# Main.net
KiCad netlist of a schematic drawn in Altium Designer
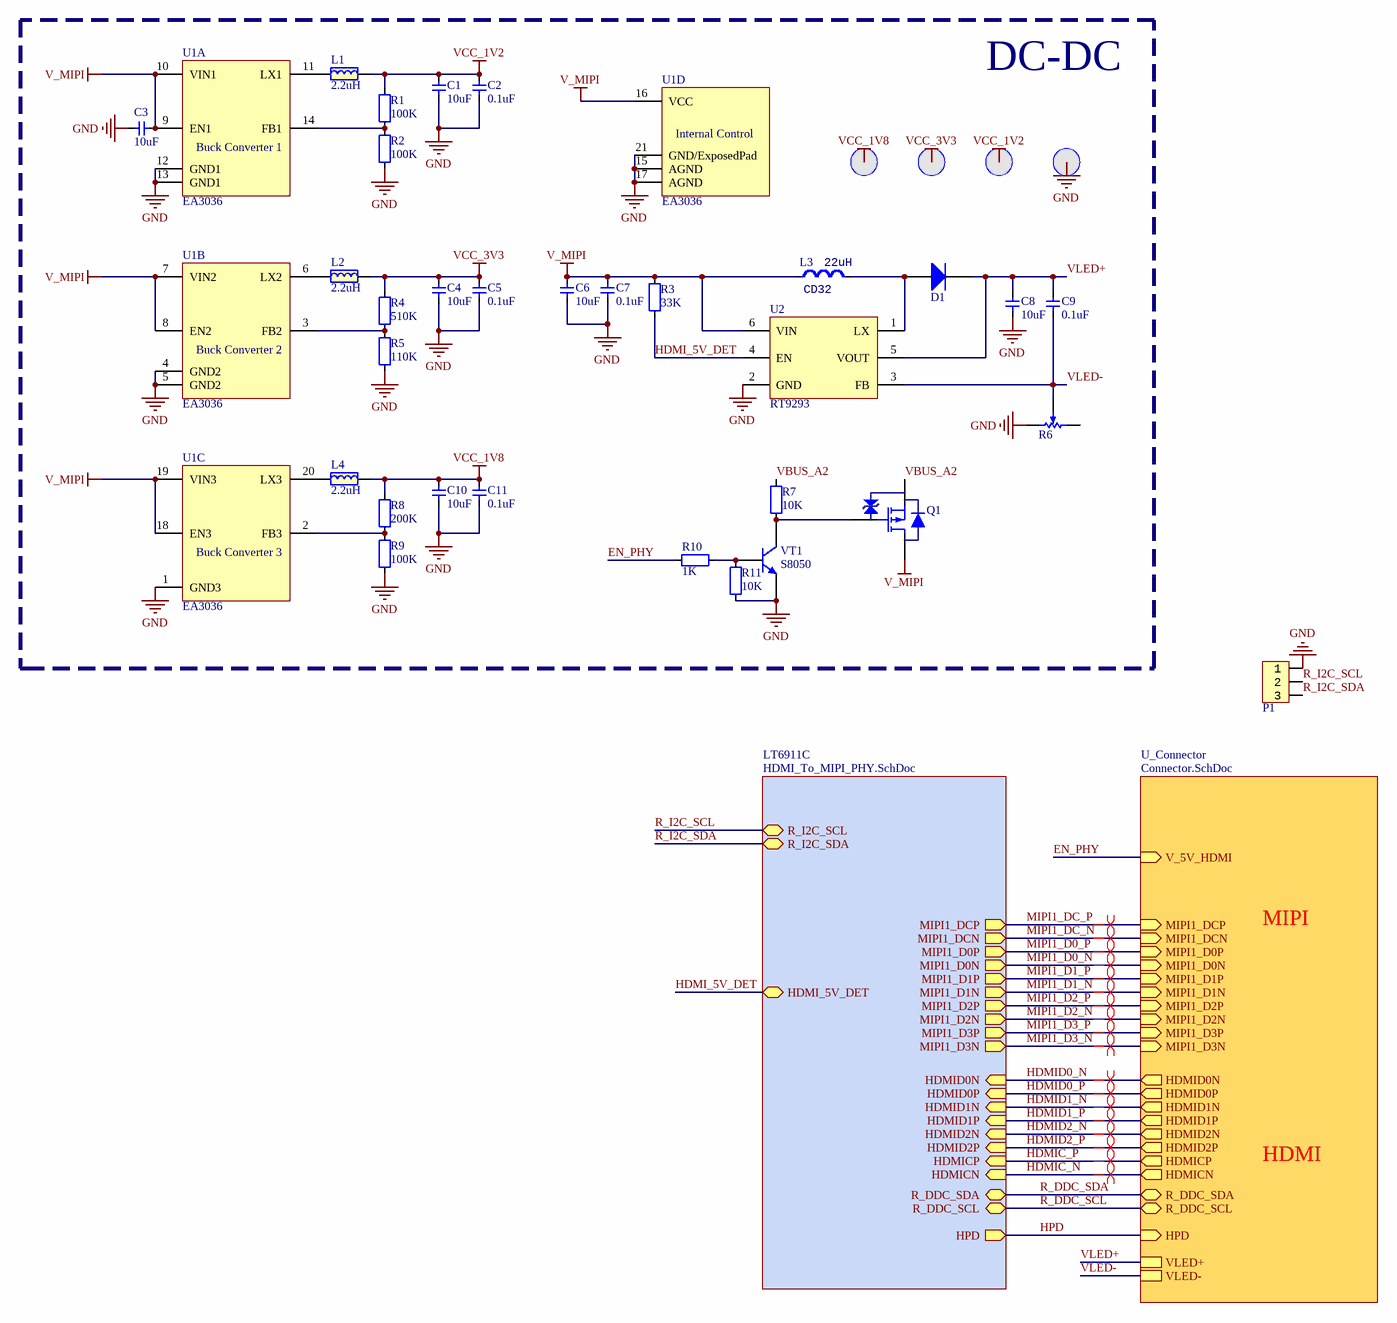
[diagram p0: Main.SchDoc]

(export (version "E")
  (design (tool "Eeschema 10.0.6"))
  (components
    (comp (ref "C1")
      (value "10uF")
      (footprint "CAP_0402")
      (description "Capacitor")
      (libsource (lib "MyPcbLib") (part "电容-0402"))
    )
    (comp (ref "C2")
      (value "0.1uF")
      (footprint "CAP_0402")
      (description "Capacitor")
      (libsource (lib "MyPcbLib") (part "电容-0402"))
    )
    (comp (ref "C3")
      (value "10uF")
      (footprint "CAP_0402")
      (description "Capacitor")
      (libsource (lib "MyPcbLib") (part "电容-0402"))
    )
    (comp (ref "C4")
      (value "10uF")
      (footprint "CAP_0402")
      (description "Capacitor")
      (libsource (lib "MyPcbLib") (part "电容-0402"))
    )
    (comp (ref "C5")
      (value "0.1uF")
      (footprint "CAP_0402")
      (description "Capacitor")
      (libsource (lib "MyPcbLib") (part "电容-0402"))
    )
    (comp (ref "C6")
      (value "10uF")
      (footprint "CAP_0402")
      (description "Capacitor")
      (libsource (lib "MyPcbLib") (part "电容-0402"))
    )
    (comp (ref "C7")
      (value "0.1uF")
      (footprint "CAP_0402")
      (description "Capacitor")
      (libsource (lib "MyPcbLib") (part "电容-0402"))
    )
    (comp (ref "C8")
      (value "10uF")
      (footprint "CAP_0402")
      (description "Capacitor")
      (libsource (lib "MyPcbLib") (part "电容-0402"))
    )
    (comp (ref "C9")
      (value "0.1uF")
      (footprint "CAP_0402")
      (description "Capacitor")
      (libsource (lib "MyPcbLib") (part "电容-0402"))
    )
    (comp (ref "C10")
      (value "10uF")
      (footprint "CAP_0402")
      (description "Capacitor")
      (libsource (lib "MyPcbLib") (part "电容-0402"))
    )
    (comp (ref "C11")
      (value "0.1uF")
      (footprint "CAP_0402")
      (description "Capacitor")
      (libsource (lib "MyPcbLib") (part "电容-0402"))
    )
    (comp (ref "D1")
      (value "二极管-5B5817WS")
      (footprint "SOD-323")
      (description "40V")
      (libsource (lib "MyPcbLib") (part "二极管-5B5817WS"))
    )
    (comp (ref "L1")
      (value "2.2uH")
      (footprint "2520-L")
      (description "磁珠")
      (libsource (lib "MyPcbLib") (part "电感-2520"))
    )
    (comp (ref "L2")
      (value "2.2uH")
      (footprint "2520-L")
      (description "磁珠")
      (libsource (lib "MyPcbLib") (part "电感-2520"))
    )
    (comp (ref "L3")
      (value "22uH")
      (footprint "IND_CD32")
      (description "Inductor")
      (fields (field (name "TYPE") "CD32") (field (name "Comment") "CD32"))
      (libsource (lib "KitSprout") (part "Ind_CD32"))
    )
    (comp (ref "L4")
      (value "2.2uH")
      (footprint "2520-L")
      (description "磁珠")
      (libsource (lib "MyPcbLib") (part "电感-2520"))
    )
    (comp (ref "P1")
      (value "HDR1x3_2.54")
      (footprint "HDR1X3_2.54_90")
      (description "Header")
      (libsource (lib "KitSprout") (part "HDR1x3_2.54T"))
    )
    (comp (ref "Q1")
      (value "AO3415A")
      (footprint "SOT23-3")
      (description "MOSFET")
      (fields (field (name "PUBLISHER") "Altium Limited"))
      (libsource (lib "MyPcbLib") (part "AO3415A"))
    )
    (comp (ref "R1")
      (value "100K")
      (footprint "RES_0402")
      (description "Resistor")
      (libsource (lib "") (part "电阻-0402_1"))
    )
    (comp (ref "R2")
      (value "100K")
      (footprint "RES_0402")
      (description "Resistor")
      (libsource (lib "") (part "电阻-0402_1"))
    )
    (comp (ref "R3")
      (value "33K")
      (footprint "RES_0402")
      (description "Resistor")
      (libsource (lib "") (part "电阻-0402_1"))
    )
    (comp (ref "R4")
      (value "510K")
      (footprint "RES_0402")
      (description "Resistor")
      (libsource (lib "") (part "电阻-0402_1"))
    )
    (comp (ref "R5")
      (value "110K")
      (footprint "RES_0402")
      (description "Resistor")
      (libsource (lib "") (part "电阻-0402_1"))
    )
    (comp (ref "R6")
      (value "电位器-贴片")
      (footprint "贴片电位器 3*3")
      (fields (field (name "PUBLISHER") "Altium Limited"))
      (libsource (lib "MyPcbLib") (part "电位器-贴片"))
    )
    (comp (ref "R7")
      (value "10K")
      (footprint "RES_0402")
      (description "Resistor")
      (libsource (lib "") (part "电阻-0402_1"))
    )
    (comp (ref "R8")
      (value "200K")
      (footprint "RES_0402")
      (description "Resistor")
      (libsource (lib "") (part "电阻-0402_1"))
    )
    (comp (ref "R9")
      (value "100K")
      (footprint "RES_0402")
      (description "Resistor")
      (libsource (lib "") (part "电阻-0402_1"))
    )
    (comp (ref "R10")
      (value "1K")
      (footprint "RES_0402")
      (description "Resistor")
      (libsource (lib "") (part "电阻-0402_2"))
    )
    (comp (ref "R11")
      (value "10K")
      (footprint "RES_0402")
      (description "Resistor")
      (libsource (lib "MyPcbLib") (part "电阻-0402"))
    )
    (comp (ref "T1") (value "测试点") (footprint "TEST_PT") (libsource (lib "MyPcbLib") (part "测试点")))
    (comp (ref "T2") (value "测试点") (footprint "TEST_PT") (libsource (lib "MyPcbLib") (part "测试点")))
    (comp (ref "T3") (value "测试点") (footprint "TEST_PT") (libsource (lib "MyPcbLib") (part "测试点")))
    (comp (ref "T4") (value "测试点") (footprint "TEST_PT") (libsource (lib "MyPcbLib") (part "测试点")))
    (comp (ref "U1") (value "EA3036") (footprint "QFN-20") (libsource (lib "MyPcbLib") (part "EA3036")))
    (comp (ref "U2")
      (value "RT9293")
      (footprint "SOT23-6")
      (description "LCD-LED Driver")
      (libsource (lib "mLib") (part "RT9293"))
    )
    (comp (ref "VT1")
      (value "S8050")
      (footprint "SMT_TRIODE_NPN")
      (description "Surface mount NPN transistor, package SOT-23")
      (libsource (lib "MyPcbLib") (part "SMT_TRIODE_NPN"))
    )
  )
  (nets
    (net (code "1") (name "/EN_PHY") (class "Default")
      (node (ref "R10") (pin "2") (pinfunction "2_2") (pintype "passive"))
    )
    (net (code "10") (name "/HDMI_5V_DET") (class "Default")
      (node (ref "R3") (pin "1") (pinfunction "1_1") (pintype "passive"))
      (node (ref "U2") (pin "4") (pinfunction "EN_4") (pintype "passive"))
    )
    (net (code "24") (name "/R_I2C_SCL") (class "Default")
      (node (ref "P1") (pin "2") (pinfunction "2_2") (pintype "passive"))
    )
    (net (code "25") (name "/R_I2C_SDA") (class "Default")
      (node (ref "P1") (pin "3") (pinfunction "3_3") (pintype "passive"))
    )
    (net (code "26") (name "/VBUS_A2") (class "Default")
      (node (ref "Q1") (pin "2") (pinfunction "S_2") (pintype "passive"))
      (node (ref "R7") (pin "2") (pinfunction "2_2") (pintype "passive"))
    )
    (net (code "27") (name "/VLED+") (class "Default")
      (node (ref "C8") (pin "2") (pinfunction "2_2") (pintype "passive"))
      (node (ref "C9") (pin "2") (pinfunction "2_2") (pintype "passive"))
      (node (ref "D1") (pin "2") (pinfunction "K_2") (pintype "passive"))
      (node (ref "U2") (pin "5") (pinfunction "VOUT_5") (pintype "passive"))
    )
    (net (code "28") (name "/VLED-") (class "Default")
      (node (ref "C9") (pin "1") (pinfunction "1_1") (pintype "passive"))
      (node (ref "R6") (pin "3") (pinfunction "W_3") (pintype "passive"))
      (node (ref "U2") (pin "3") (pinfunction "FB_3") (pintype "passive"))
    )
    (net (code "29") (name "GND") (class "Default")
      (node (ref "C1") (pin "2") (pinfunction "2_2") (pintype "passive"))
      (node (ref "C10") (pin "2") (pinfunction "2_2") (pintype "passive"))
      (node (ref "C11") (pin "2") (pinfunction "2_2") (pintype "passive"))
      (node (ref "C2") (pin "2") (pinfunction "2_2") (pintype "passive"))
      (node (ref "C3") (pin "1") (pinfunction "1_1") (pintype "passive"))
      (node (ref "C4") (pin "2") (pinfunction "2_2") (pintype "passive"))
      (node (ref "C5") (pin "2") (pinfunction "2_2") (pintype "passive"))
      (node (ref "C6") (pin "1") (pinfunction "1_1") (pintype "passive"))
      (node (ref "C7") (pin "1") (pinfunction "1_1") (pintype "passive"))
      (node (ref "C8") (pin "1") (pinfunction "1_1") (pintype "passive"))
      (node (ref "P1") (pin "1") (pinfunction "1_1") (pintype "passive"))
      (node (ref "R11") (pin "2") (pinfunction "2_2") (pintype "passive"))
      (node (ref "R2") (pin "1") (pinfunction "1_1") (pintype "passive"))
      (node (ref "R5") (pin "1") (pinfunction "1_1") (pintype "passive"))
      (node (ref "R6") (pin "1") (pinfunction "+_1") (pintype "passive"))
      (node (ref "R9") (pin "1") (pinfunction "1_1") (pintype "passive"))
      (node (ref "T4") (pin "0") (pinfunction "0_0") (pintype "passive"))
      (node (ref "U1") (pin "1") (pinfunction "GND3_1") (pintype "power_in"))
      (node (ref "U1") (pin "12") (pinfunction "GND1_12") (pintype "power_in"))
      (node (ref "U1") (pin "13") (pinfunction "GND1_13") (pintype "power_in"))
      (node (ref "U1") (pin "15") (pinfunction "AGND_15") (pintype "power_in"))
      (node (ref "U1") (pin "17") (pinfunction "AGND_17") (pintype "power_in"))
      (node (ref "U1") (pin "21") (pinfunction "GND/ExposedPad_21") (pintype "power_in"))
      (node (ref "U1") (pin "4") (pinfunction "GND2_4") (pintype "power_in"))
      (node (ref "U1") (pin "5") (pinfunction "GND2_5") (pintype "power_in"))
      (node (ref "U2") (pin "2") (pinfunction "GND_2") (pintype "passive"))
      (node (ref "VT1") (pin "2") (pinfunction "E_2") (pintype "passive"))
    )
    (net (code "30") (name "Net-(D1-A)") (class "Default")
      (node (ref "D1") (pin "1") (pinfunction "A_1") (pintype "passive"))
      (node (ref "L3") (pin "2") (pinfunction "2_2") (pintype "passive"))
      (node (ref "U2") (pin "1") (pinfunction "LX_1") (pintype "passive"))
    )
    (net (code "31") (name "Net-(Q1-G)") (class "Default")
      (node (ref "Q1") (pin "1") (pinfunction "G_1") (pintype "passive"))
      (node (ref "R7") (pin "1") (pinfunction "1_1") (pintype "passive"))
      (node (ref "VT1") (pin "3") (pinfunction "C_3") (pintype "passive"))
    )
    (net (code "32") (name "Net-(U1A-FB1)") (class "Default")
      (node (ref "R1") (pin "1") (pinfunction "1_1") (pintype "passive"))
      (node (ref "R2") (pin "2") (pinfunction "2_2") (pintype "passive"))
      (node (ref "U1") (pin "14") (pinfunction "FB1_14") (pintype "passive"))
    )
    (net (code "33") (name "Net-(U1A-LX1)") (class "Default")
      (node (ref "L1") (pin "1") (pintype "passive"))
      (node (ref "U1") (pin "11") (pinfunction "LX1_11") (pintype "passive"))
    )
    (net (code "34") (name "Net-(U1B-FB2)") (class "Default")
      (node (ref "R4") (pin "1") (pinfunction "1_1") (pintype "passive"))
      (node (ref "R5") (pin "2") (pinfunction "2_2") (pintype "passive"))
      (node (ref "U1") (pin "3") (pinfunction "FB2_3") (pintype "passive"))
    )
    (net (code "35") (name "Net-(U1B-LX2)") (class "Default")
      (node (ref "L2") (pin "1") (pintype "passive"))
      (node (ref "U1") (pin "6") (pinfunction "LX2_6") (pintype "passive"))
    )
    (net (code "36") (name "Net-(U1C-FB3)") (class "Default")
      (node (ref "R8") (pin "1") (pinfunction "1_1") (pintype "passive"))
      (node (ref "R9") (pin "2") (pinfunction "2_2") (pintype "passive"))
      (node (ref "U1") (pin "2") (pinfunction "FB3_2") (pintype "passive"))
    )
    (net (code "37") (name "Net-(U1C-LX3)") (class "Default")
      (node (ref "L4") (pin "1") (pintype "passive"))
      (node (ref "U1") (pin "20") (pinfunction "LX3_20") (pintype "passive"))
    )
    (net (code "38") (name "Net-(VT1-B)") (class "Default")
      (node (ref "R10") (pin "1") (pinfunction "1_1") (pintype "passive"))
      (node (ref "R11") (pin "1") (pinfunction "1_1") (pintype "passive"))
      (node (ref "VT1") (pin "1") (pinfunction "B_1") (pintype "passive"))
    )
    (net (code "39") (name "VCC_1V2") (class "Default")
      (node (ref "C1") (pin "1") (pinfunction "1_1") (pintype "passive"))
      (node (ref "C2") (pin "1") (pinfunction "1_1") (pintype "passive"))
      (node (ref "L1") (pin "2") (pinfunction "2_2") (pintype "passive"))
      (node (ref "R1") (pin "2") (pinfunction "2_2") (pintype "passive"))
      (node (ref "T3") (pin "0") (pinfunction "0_0") (pintype "passive"))
    )
    (net (code "40") (name "VCC_1V8") (class "Default")
      (node (ref "C10") (pin "1") (pinfunction "1_1") (pintype "passive"))
      (node (ref "C11") (pin "1") (pinfunction "1_1") (pintype "passive"))
      (node (ref "L4") (pin "2") (pinfunction "2_2") (pintype "passive"))
      (node (ref "R8") (pin "2") (pinfunction "2_2") (pintype "passive"))
      (node (ref "T1") (pin "0") (pinfunction "0_0") (pintype "passive"))
    )
    (net (code "41") (name "VCC_3V3") (class "Default")
      (node (ref "C4") (pin "1") (pinfunction "1_1") (pintype "passive"))
      (node (ref "C5") (pin "1") (pinfunction "1_1") (pintype "passive"))
      (node (ref "L2") (pin "2") (pinfunction "2_2") (pintype "passive"))
      (node (ref "R4") (pin "2") (pinfunction "2_2") (pintype "passive"))
      (node (ref "T2") (pin "0") (pinfunction "0_0") (pintype "passive"))
    )
    (net (code "42") (name "V_MIPI") (class "Default")
      (node (ref "C3") (pin "2") (pinfunction "2_2") (pintype "passive"))
      (node (ref "C6") (pin "2") (pinfunction "2_2") (pintype "passive"))
      (node (ref "C7") (pin "2") (pinfunction "2_2") (pintype "passive"))
      (node (ref "L3") (pin "1") (pinfunction "1_1") (pintype "passive"))
      (node (ref "Q1") (pin "3") (pinfunction "D_3") (pintype "passive"))
      (node (ref "R3") (pin "2") (pinfunction "2_2") (pintype "passive"))
      (node (ref "U1") (pin "10") (pinfunction "VIN1_10") (pintype "power_in"))
      (node (ref "U1") (pin "16") (pinfunction "VCC_16") (pintype "power_in"))
      (node (ref "U1") (pin "18") (pinfunction "EN3_18") (pintype "passive"))
      (node (ref "U1") (pin "19") (pinfunction "VIN3_19") (pintype "power_in"))
      (node (ref "U1") (pin "7") (pinfunction "VIN2_7") (pintype "power_in"))
      (node (ref "U1") (pin "8") (pinfunction "EN2_8") (pintype "passive"))
      (node (ref "U1") (pin "9") (pinfunction "EN1_9") (pintype "passive"))
      (node (ref "U2") (pin "6") (pinfunction "VIN_6") (pintype "passive"))
    )
    (net (code "43") (name "unconnected-(R6---Pad2)") (class "Default")
      (node (ref "R6") (pin "2") (pinfunction "-_2") (pintype "passive"))
    )
  )
)
